# heart-beat.net
KiCad netlist of a schematic drawn in EAGLE
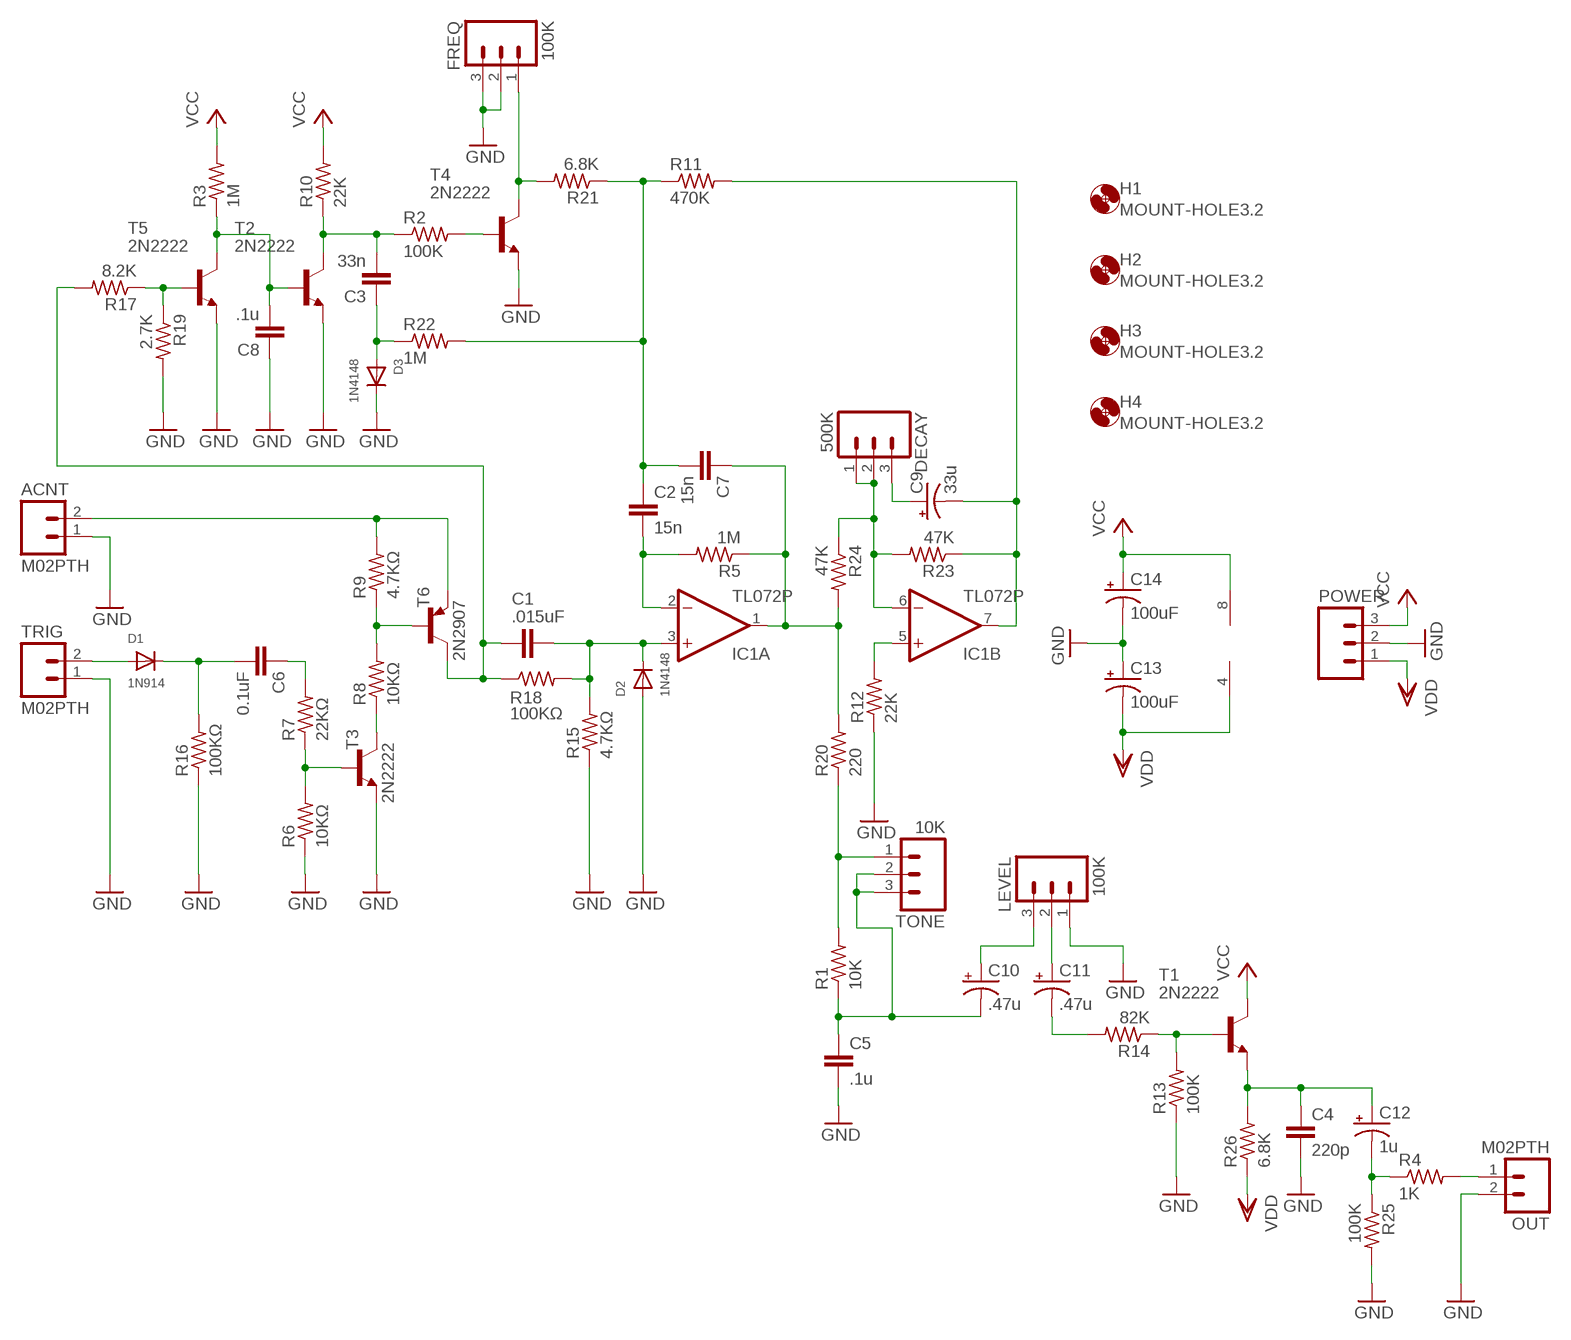
[diagram p0: schematic, sheet 1]

(export (version "E")
  (design (tool "Eeschema 10.0.6"))
  (components
    (comp (ref "ACNT")
      (value "M02PTH")
      (footprint "eagle-import:1X02")
      (libsource (lib "eagle-import") (part "M02PTH"))
    )
    (comp (ref "C1")
      (value ".015uF")
      (footprint "eagle-import:C025-024X044")
      (libsource (lib "eagle-import") (part "C-EU025-024X044"))
    )
    (comp (ref "C2")
      (value "15n")
      (footprint "eagle-import:C025-024X044")
      (libsource (lib "eagle-import") (part "C-EU025-024X044"))
    )
    (comp (ref "C3")
      (value "33n")
      (footprint "eagle-import:C025-024X044")
      (libsource (lib "eagle-import") (part "C-EU025-024X044"))
    )
    (comp (ref "C4")
      (value "220p")
      (footprint "eagle-import:C025-024X044")
      (libsource (lib "eagle-import") (part "C-EU025-024X044"))
    )
    (comp (ref "C5")
      (value ".1u")
      (footprint "eagle-import:C025-024X044")
      (libsource (lib "eagle-import") (part "C-EU025-024X044"))
    )
    (comp (ref "C6")
      (value "0.1uF")
      (footprint "eagle-import:C025-024X044")
      (libsource (lib "eagle-import") (part "C-EU025-024X044"))
    )
    (comp (ref "C7")
      (value "15n")
      (footprint "eagle-import:C025-024X044")
      (libsource (lib "eagle-import") (part "C-EU025-024X044"))
    )
    (comp (ref "C8")
      (value ".1u")
      (footprint "eagle-import:C025-024X044")
      (libsource (lib "eagle-import") (part "C-EU025-024X044"))
    )
    (comp (ref "C9")
      (value "33u")
      (footprint "eagle-import:E2,5-6E")
      (libsource (lib "eagle-import") (part "CPOL-USE2,5-6E"))
    )
    (comp (ref "C10")
      (value ".47u")
      (footprint "eagle-import:E2,5-6E")
      (libsource (lib "eagle-import") (part "CPOL-USE2,5-6E"))
    )
    (comp (ref "C11")
      (value ".47u")
      (footprint "eagle-import:E2,5-6E")
      (libsource (lib "eagle-import") (part "CPOL-USE2,5-6E"))
    )
    (comp (ref "C12")
      (value "1u")
      (footprint "eagle-import:E2,5-6E")
      (libsource (lib "eagle-import") (part "CPOL-USE2,5-6E"))
    )
    (comp (ref "C13")
      (value "100uF")
      (footprint "eagle-import:E2,5-6E")
      (libsource (lib "eagle-import") (part "CPOL-USE2,5-6E"))
    )
    (comp (ref "C14")
      (value "100uF")
      (footprint "eagle-import:E2,5-6E")
      (libsource (lib "eagle-import") (part "CPOL-USE2,5-6E"))
    )
    (comp (ref "D1")
      (value "1N914")
      (footprint "eagle-import:1N4148")
      (libsource (lib "eagle-import") (part "DIODE"))
    )
    (comp (ref "D2")
      (value "1N4148")
      (footprint "eagle-import:1N4148")
      (libsource (lib "eagle-import") (part "DIODE"))
    )
    (comp (ref "D3")
      (value "1N4148")
      (footprint "eagle-import:1N4148")
      (libsource (lib "eagle-import") (part "DIODE"))
    )
    (comp (ref "DECAY")
      (value "500K")
      (footprint "eagle-import:1X03")
      (libsource (lib "eagle-import") (part "M03PTH"))
    )
    (comp (ref "FREQ")
      (value "100K")
      (footprint "eagle-import:1X03")
      (libsource (lib "eagle-import") (part "M03PTH"))
    )
    (comp (ref "H1")
      (value "MOUNT-HOLE3.2")
      (footprint "eagle-import:3,2")
      (libsource (lib "eagle-import") (part "MOUNT-HOLE3.2"))
    )
    (comp (ref "H2")
      (value "MOUNT-HOLE3.2")
      (footprint "eagle-import:3,2")
      (libsource (lib "eagle-import") (part "MOUNT-HOLE3.2"))
    )
    (comp (ref "H3")
      (value "MOUNT-HOLE3.2")
      (footprint "eagle-import:3,2")
      (libsource (lib "eagle-import") (part "MOUNT-HOLE3.2"))
    )
    (comp (ref "H4")
      (value "MOUNT-HOLE3.2")
      (footprint "eagle-import:3,2")
      (libsource (lib "eagle-import") (part "MOUNT-HOLE3.2"))
    )
    (comp (ref "IC1")
      (value "TL072P")
      (footprint "eagle-import:DIL08")
      (libsource (lib "eagle-import") (part "TL072P"))
    )
    (comp (ref "LEVEL")
      (value "100K")
      (footprint "eagle-import:1X03")
      (libsource (lib "eagle-import") (part "M03PTH"))
    )
    (comp (ref "OUT")
      (value "M02PTH")
      (footprint "eagle-import:1X02")
      (libsource (lib "eagle-import") (part "M02PTH"))
    )
    (comp (ref "POWER")
      (value "M03PTH")
      (footprint "eagle-import:1X03")
      (libsource (lib "eagle-import") (part "M03PTH"))
    )
    (comp (ref "R1")
      (value "10K")
      (footprint "eagle-import:0204_5")
      (libsource (lib "eagle-import") (part "R-US_0204/5"))
    )
    (comp (ref "R2")
      (value "100K")
      (footprint "eagle-import:0204_5")
      (libsource (lib "eagle-import") (part "R-US_0204/5"))
    )
    (comp (ref "R3")
      (value "1M")
      (footprint "eagle-import:0204_5")
      (libsource (lib "eagle-import") (part "R-US_0204/5"))
    )
    (comp (ref "R4")
      (value "1K")
      (footprint "eagle-import:0204_5")
      (libsource (lib "eagle-import") (part "R-US_0204/5"))
    )
    (comp (ref "R5")
      (value "1M")
      (footprint "eagle-import:0204_5")
      (libsource (lib "eagle-import") (part "R-US_0204/5"))
    )
    (comp (ref "R6")
      (value "10KΩ")
      (footprint "eagle-import:0204_5")
      (libsource (lib "eagle-import") (part "R-US_0204/5"))
    )
    (comp (ref "R7")
      (value "22KΩ")
      (footprint "eagle-import:0204_5")
      (libsource (lib "eagle-import") (part "R-US_0204/5"))
    )
    (comp (ref "R8")
      (value "10KΩ")
      (footprint "eagle-import:0204_5")
      (libsource (lib "eagle-import") (part "R-US_0204/5"))
    )
    (comp (ref "R9")
      (value "4.7KΩ")
      (footprint "eagle-import:0204_5")
      (libsource (lib "eagle-import") (part "R-US_0204/5"))
    )
    (comp (ref "R10")
      (value "22K")
      (footprint "eagle-import:0204_5")
      (libsource (lib "eagle-import") (part "R-US_0204/5"))
    )
    (comp (ref "R11")
      (value "470K")
      (footprint "eagle-import:0204_5")
      (libsource (lib "eagle-import") (part "R-US_0204/5"))
    )
    (comp (ref "R12")
      (value "22K")
      (footprint "eagle-import:0204_5")
      (libsource (lib "eagle-import") (part "R-US_0204/5"))
    )
    (comp (ref "R13")
      (value "100K")
      (footprint "eagle-import:0204_5")
      (libsource (lib "eagle-import") (part "R-US_0204/5"))
    )
    (comp (ref "R14")
      (value "82K")
      (footprint "eagle-import:0204_5")
      (libsource (lib "eagle-import") (part "R-US_0204/5"))
    )
    (comp (ref "R15")
      (value "4.7KΩ")
      (footprint "eagle-import:0204_5")
      (libsource (lib "eagle-import") (part "R-US_0204/5"))
    )
    (comp (ref "R16")
      (value "100KΩ")
      (footprint "eagle-import:0204_5")
      (libsource (lib "eagle-import") (part "R-US_0204/5"))
    )
    (comp (ref "R17")
      (value "8.2K")
      (footprint "eagle-import:0204_5")
      (libsource (lib "eagle-import") (part "R-US_0204/5"))
    )
    (comp (ref "R18")
      (value "100KΩ")
      (footprint "eagle-import:0204_5")
      (libsource (lib "eagle-import") (part "R-US_0204/5"))
    )
    (comp (ref "R19")
      (value "2.7K")
      (footprint "eagle-import:0204_5")
      (libsource (lib "eagle-import") (part "R-US_0204/5"))
    )
    (comp (ref "R20")
      (value "220")
      (footprint "eagle-import:0204_5")
      (libsource (lib "eagle-import") (part "R-US_0204/5"))
    )
    (comp (ref "R21")
      (value "6.8K")
      (footprint "eagle-import:0204_5")
      (libsource (lib "eagle-import") (part "R-US_0204/5"))
    )
    (comp (ref "R22")
      (value "1M")
      (footprint "eagle-import:0204_5")
      (libsource (lib "eagle-import") (part "R-US_0204/5"))
    )
    (comp (ref "R23")
      (value "47K")
      (footprint "eagle-import:0204_5")
      (libsource (lib "eagle-import") (part "R-US_0204/5"))
    )
    (comp (ref "R24")
      (value "47K")
      (footprint "eagle-import:0204_5")
      (libsource (lib "eagle-import") (part "R-US_0204/5"))
    )
    (comp (ref "R25")
      (value "100K")
      (footprint "eagle-import:0204_5")
      (libsource (lib "eagle-import") (part "R-US_0204/5"))
    )
    (comp (ref "R26")
      (value "6.8K")
      (footprint "eagle-import:0204_5")
      (libsource (lib "eagle-import") (part "R-US_0204/5"))
    )
    (comp (ref "T1")
      (value "2N2222")
      (footprint "eagle-import:TO92-EBC-OVAL")
      (libsource (lib "eagle-import") (part "2N2222"))
    )
    (comp (ref "T2")
      (value "2N2222")
      (footprint "eagle-import:TO92-EBC-OVAL")
      (libsource (lib "eagle-import") (part "2N2222"))
    )
    (comp (ref "T3")
      (value "2N2222")
      (footprint "eagle-import:TO92-EBC-OVAL")
      (libsource (lib "eagle-import") (part "2N2222"))
    )
    (comp (ref "T4")
      (value "2N2222")
      (footprint "eagle-import:TO92-EBC-OVAL")
      (libsource (lib "eagle-import") (part "2N2222"))
    )
    (comp (ref "T5")
      (value "2N2222")
      (footprint "eagle-import:TO92-EBC-OVAL")
      (libsource (lib "eagle-import") (part "2N2222"))
    )
    (comp (ref "T6")
      (value "2N2907")
      (footprint "eagle-import:TO92-EBC-OVAL")
      (libsource (lib "eagle-import") (part "2N2907"))
    )
    (comp (ref "TONE")
      (value "10K")
      (footprint "eagle-import:1X03")
      (libsource (lib "eagle-import") (part "M03PTH"))
    )
    (comp (ref "TRIG")
      (value "M02PTH")
      (footprint "eagle-import:1X02")
      (libsource (lib "eagle-import") (part "M02PTH"))
    )
  )
  (nets
    (net (code "1") (name "GND") (class "Default")
      (node (ref "ACNT") (pin "1") (pinfunction "1_1") (pintype "passive"))
      (node (ref "C13") (pin "+") (pinfunction "+_+") (pintype "passive"))
      (node (ref "C14") (pin "-") (pinfunction "-_-") (pintype "passive"))
      (node (ref "C4") (pin "2") (pinfunction "2_2") (pintype "passive"))
      (node (ref "C5") (pin "2") (pinfunction "2_2") (pintype "passive"))
      (node (ref "C8") (pin "1") (pinfunction "1_1") (pintype "passive"))
      (node (ref "D2") (pin "A") (pinfunction "A_A") (pintype "passive"))
      (node (ref "D3") (pin "K") (pinfunction "C_K") (pintype "passive"))
      (node (ref "FREQ") (pin "2") (pinfunction "2_2") (pintype "passive"))
      (node (ref "FREQ") (pin "3") (pinfunction "3_3") (pintype "passive"))
      (node (ref "LEVEL") (pin "1") (pinfunction "1_1") (pintype "passive"))
      (node (ref "OUT") (pin "2") (pinfunction "2_2") (pintype "passive"))
      (node (ref "POWER") (pin "2") (pinfunction "2_2") (pintype "passive"))
      (node (ref "R12") (pin "1") (pinfunction "1_1") (pintype "passive"))
      (node (ref "R13") (pin "1") (pinfunction "1_1") (pintype "passive"))
      (node (ref "R15") (pin "1") (pinfunction "1_1") (pintype "passive"))
      (node (ref "R16") (pin "1") (pinfunction "1_1") (pintype "passive"))
      (node (ref "R19") (pin "2") (pinfunction "2_2") (pintype "passive"))
      (node (ref "R25") (pin "2") (pinfunction "2_2") (pintype "passive"))
      (node (ref "R6") (pin "1") (pinfunction "1_1") (pintype "passive"))
      (node (ref "T2") (pin "E") (pinfunction "E_E") (pintype "passive"))
      (node (ref "T3") (pin "E") (pinfunction "E_E") (pintype "passive"))
      (node (ref "T4") (pin "E") (pinfunction "E_E") (pintype "passive"))
      (node (ref "T5") (pin "E") (pinfunction "E_E") (pintype "passive"))
      (node (ref "TRIG") (pin "1") (pinfunction "1_1") (pintype "passive"))
    )
    (net (code "2") (name "Net-(ACNT-Pad2)") (class "Default")
      (node (ref "ACNT") (pin "2") (pinfunction "2_2") (pintype "passive"))
      (node (ref "R9") (pin "2") (pinfunction "2_2") (pintype "passive"))
      (node (ref "T6") (pin "E") (pinfunction "E_E") (pintype "passive"))
    )
    (net (code "3") (name "Net-(C1-Pad2)") (class "Default")
      (node (ref "C1") (pin "2") (pinfunction "2_2") (pintype "passive"))
      (node (ref "R17") (pin "2") (pinfunction "2_2") (pintype "passive"))
      (node (ref "R18") (pin "1") (pinfunction "1_1") (pintype "passive"))
      (node (ref "T6") (pin "C") (pinfunction "C_C") (pintype "passive"))
    )
    (net (code "4") (name "Net-(C2-Pad1)") (class "Default")
      (node (ref "C2") (pin "1") (pinfunction "1_1") (pintype "passive"))
      (node (ref "C7") (pin "2") (pinfunction "2_2") (pintype "passive"))
      (node (ref "R11") (pin "1") (pinfunction "1_1") (pintype "passive"))
      (node (ref "R21") (pin "1") (pinfunction "1_1") (pintype "passive"))
      (node (ref "R22") (pin "2") (pinfunction "2_2") (pintype "passive"))
    )
    (net (code "5") (name "Net-(C3-Pad1)") (class "Default")
      (node (ref "C3") (pin "1") (pinfunction "1_1") (pintype "passive"))
      (node (ref "D3") (pin "A") (pinfunction "A_A") (pintype "passive"))
      (node (ref "R22") (pin "1") (pinfunction "1_1") (pintype "passive"))
    )
    (net (code "6") (name "Net-(C3-Pad2)") (class "Default")
      (node (ref "C3") (pin "2") (pinfunction "2_2") (pintype "passive"))
      (node (ref "R10") (pin "1") (pinfunction "1_1") (pintype "passive"))
      (node (ref "R2") (pin "1") (pinfunction "1_1") (pintype "passive"))
      (node (ref "T2") (pin "C") (pinfunction "C_C") (pintype "passive"))
    )
    (net (code "7") (name "Net-(C6-Pad1)") (class "Default")
      (node (ref "C6") (pin "1") (pinfunction "1_1") (pintype "passive"))
      (node (ref "R7") (pin "2") (pinfunction "2_2") (pintype "passive"))
    )
    (net (code "8") (name "Net-(C8-Pad2)") (class "Default")
      (node (ref "C8") (pin "2") (pinfunction "2_2") (pintype "passive"))
      (node (ref "R3") (pin "1") (pinfunction "1_1") (pintype "passive"))
      (node (ref "T2") (pin "B") (pinfunction "B_B") (pintype "passive"))
      (node (ref "T5") (pin "C") (pinfunction "C_C") (pintype "passive"))
    )
    (net (code "9") (name "Net-(C9-Pad+)") (class "Default")
      (node (ref "C9") (pin "+") (pinfunction "+_+") (pintype "passive"))
      (node (ref "DECAY") (pin "3") (pinfunction "3_3") (pintype "passive"))
    )
    (net (code "10") (name "Net-(C10-Pad+)") (class "Default")
      (node (ref "C10") (pin "+") (pinfunction "+_+") (pintype "passive"))
      (node (ref "LEVEL") (pin "3") (pinfunction "3_3") (pintype "passive"))
    )
    (net (code "11") (name "Net-(C10-Pad-)") (class "Default")
      (node (ref "C10") (pin "-") (pinfunction "-_-") (pintype "passive"))
      (node (ref "C5") (pin "1") (pinfunction "1_1") (pintype "passive"))
      (node (ref "R1") (pin "1") (pinfunction "1_1") (pintype "passive"))
      (node (ref "TONE") (pin "2") (pinfunction "2_2") (pintype "passive"))
      (node (ref "TONE") (pin "3") (pinfunction "3_3") (pintype "passive"))
    )
    (net (code "12") (name "Net-(C11-Pad+)") (class "Default")
      (node (ref "C11") (pin "+") (pinfunction "+_+") (pintype "passive"))
      (node (ref "LEVEL") (pin "2") (pinfunction "2_2") (pintype "passive"))
    )
    (net (code "13") (name "Net-(C11-Pad-)") (class "Default")
      (node (ref "C11") (pin "-") (pinfunction "-_-") (pintype "passive"))
      (node (ref "R14") (pin "2") (pinfunction "2_2") (pintype "passive"))
    )
    (net (code "14") (name "Net-(C12-Pad+)") (class "Default")
      (node (ref "C12") (pin "+") (pinfunction "+_+") (pintype "passive"))
      (node (ref "C4") (pin "1") (pinfunction "1_1") (pintype "passive"))
      (node (ref "R26") (pin "2") (pinfunction "2_2") (pintype "passive"))
      (node (ref "T1") (pin "E") (pinfunction "E_E") (pintype "passive"))
    )
    (net (code "15") (name "Net-(C12-Pad-)") (class "Default")
      (node (ref "C12") (pin "-") (pinfunction "-_-") (pintype "passive"))
      (node (ref "R25") (pin "1") (pinfunction "1_1") (pintype "passive"))
      (node (ref "R4") (pin "1") (pinfunction "1_1") (pintype "passive"))
    )
    (net (code "16") (name "Net-(D1-C)") (class "Default")
      (node (ref "C6") (pin "2") (pinfunction "2_2") (pintype "passive"))
      (node (ref "D1") (pin "K") (pinfunction "C_K") (pintype "passive"))
      (node (ref "R16") (pin "2") (pinfunction "2_2") (pintype "passive"))
    )
    (net (code "17") (name "Net-(D1-PadA)") (class "Default")
      (node (ref "D1") (pin "A") (pinfunction "A_A") (pintype "passive"))
      (node (ref "TRIG") (pin "2") (pinfunction "2_2") (pintype "passive"))
    )
    (net (code "18") (name "Net-(D2-C)") (class "Default")
      (node (ref "C1") (pin "1") (pinfunction "1_1") (pintype "passive"))
      (node (ref "D2") (pin "K") (pinfunction "C_K") (pintype "passive"))
      (node (ref "IC1") (pin "3") (pinfunction "+IN_3") (pintype "input"))
      (node (ref "R15") (pin "2") (pinfunction "2_2") (pintype "passive"))
      (node (ref "R18") (pin "2") (pinfunction "2_2") (pintype "passive"))
    )
    (net (code "19") (name "Net-(FREQ-Pad1)") (class "Default")
      (node (ref "FREQ") (pin "1") (pinfunction "1_1") (pintype "passive"))
      (node (ref "R21") (pin "2") (pinfunction "2_2") (pintype "passive"))
      (node (ref "T4") (pin "C") (pinfunction "C_C") (pintype "passive"))
    )
    (net (code "20") (name "Net-(IC1A--IN)") (class "Default")
      (node (ref "C2") (pin "2") (pinfunction "2_2") (pintype "passive"))
      (node (ref "IC1") (pin "2") (pinfunction "-IN_2") (pintype "input"))
      (node (ref "R5") (pin "2") (pinfunction "2_2") (pintype "passive"))
    )
    (net (code "21") (name "Net-(IC1A-OUT)") (class "Default")
      (node (ref "C7") (pin "1") (pinfunction "1_1") (pintype "passive"))
      (node (ref "IC1") (pin "1") (pinfunction "OUT_1") (pintype "output"))
      (node (ref "R20") (pin "2") (pinfunction "2_2") (pintype "passive"))
      (node (ref "R24") (pin "2") (pinfunction "2_2") (pintype "passive"))
      (node (ref "R5") (pin "1") (pinfunction "1_1") (pintype "passive"))
    )
    (net (code "22") (name "Net-(IC1B-+IN)") (class "Default")
      (node (ref "IC1") (pin "5") (pinfunction "+IN_5") (pintype "input"))
      (node (ref "R12") (pin "2") (pinfunction "2_2") (pintype "passive"))
    )
    (net (code "23") (name "Net-(IC1B--IN)") (class "Default")
      (node (ref "DECAY") (pin "1") (pinfunction "1_1") (pintype "passive"))
      (node (ref "DECAY") (pin "2") (pinfunction "2_2") (pintype "passive"))
      (node (ref "IC1") (pin "6") (pinfunction "-IN_6") (pintype "input"))
      (node (ref "R23") (pin "2") (pinfunction "2_2") (pintype "passive"))
      (node (ref "R24") (pin "1") (pinfunction "1_1") (pintype "passive"))
    )
    (net (code "24") (name "Net-(IC1B-OUT)") (class "Default")
      (node (ref "C9") (pin "-") (pinfunction "-_-") (pintype "passive"))
      (node (ref "IC1") (pin "7") (pinfunction "OUT_7") (pintype "output"))
      (node (ref "R11") (pin "2") (pinfunction "2_2") (pintype "passive"))
      (node (ref "R23") (pin "1") (pinfunction "1_1") (pintype "passive"))
    )
    (net (code "25") (name "Net-(OUT-Pad1)") (class "Default")
      (node (ref "OUT") (pin "1") (pinfunction "1_1") (pintype "passive"))
      (node (ref "R4") (pin "2") (pinfunction "2_2") (pintype "passive"))
    )
    (net (code "26") (name "Net-(R1-Pad2)") (class "Default")
      (node (ref "R1") (pin "2") (pinfunction "2_2") (pintype "passive"))
      (node (ref "R20") (pin "1") (pinfunction "1_1") (pintype "passive"))
      (node (ref "TONE") (pin "1") (pinfunction "1_1") (pintype "passive"))
    )
    (net (code "27") (name "Net-(R2-Pad2)") (class "Default")
      (node (ref "R2") (pin "2") (pinfunction "2_2") (pintype "passive"))
      (node (ref "T4") (pin "B") (pinfunction "B_B") (pintype "passive"))
    )
    (net (code "28") (name "Net-(R6-Pad2)") (class "Default")
      (node (ref "R6") (pin "2") (pinfunction "2_2") (pintype "passive"))
      (node (ref "R7") (pin "1") (pinfunction "1_1") (pintype "passive"))
      (node (ref "T3") (pin "B") (pinfunction "B_B") (pintype "passive"))
    )
    (net (code "29") (name "Net-(R8-Pad1)") (class "Default")
      (node (ref "R8") (pin "1") (pinfunction "1_1") (pintype "passive"))
      (node (ref "T3") (pin "C") (pinfunction "C_C") (pintype "passive"))
    )
    (net (code "30") (name "Net-(R8-Pad2)") (class "Default")
      (node (ref "R8") (pin "2") (pinfunction "2_2") (pintype "passive"))
      (node (ref "R9") (pin "1") (pinfunction "1_1") (pintype "passive"))
      (node (ref "T6") (pin "B") (pinfunction "B_B") (pintype "passive"))
    )
    (net (code "31") (name "Net-(R13-Pad2)") (class "Default")
      (node (ref "R13") (pin "2") (pinfunction "2_2") (pintype "passive"))
      (node (ref "R14") (pin "1") (pinfunction "1_1") (pintype "passive"))
      (node (ref "T1") (pin "B") (pinfunction "B_B") (pintype "passive"))
    )
    (net (code "32") (name "Net-(R17-Pad1)") (class "Default")
      (node (ref "R17") (pin "1") (pinfunction "1_1") (pintype "passive"))
      (node (ref "R19") (pin "1") (pinfunction "1_1") (pintype "passive"))
      (node (ref "T5") (pin "B") (pinfunction "B_B") (pintype "passive"))
    )
    (net (code "33") (name "VCC") (class "Default")
      (node (ref "C14") (pin "+") (pinfunction "+_+") (pintype "passive"))
      (node (ref "IC1") (pin "8") (pinfunction "V+_8") (pintype "power_in"))
      (node (ref "POWER") (pin "3") (pinfunction "3_3") (pintype "passive"))
      (node (ref "R10") (pin "2") (pinfunction "2_2") (pintype "passive"))
      (node (ref "R3") (pin "2") (pinfunction "2_2") (pintype "passive"))
      (node (ref "T1") (pin "C") (pinfunction "C_C") (pintype "passive"))
    )
    (net (code "34") (name "VDD") (class "Default")
      (node (ref "C13") (pin "-") (pinfunction "-_-") (pintype "passive"))
      (node (ref "IC1") (pin "4") (pinfunction "V-_4") (pintype "power_in"))
      (node (ref "POWER") (pin "1") (pinfunction "1_1") (pintype "passive"))
      (node (ref "R26") (pin "1") (pinfunction "1_1") (pintype "passive"))
    )
  )
)
